# SAMW25_Xplained_Pro_EDBG.net
KiCad netlist of a schematic drawn in Altium Designer
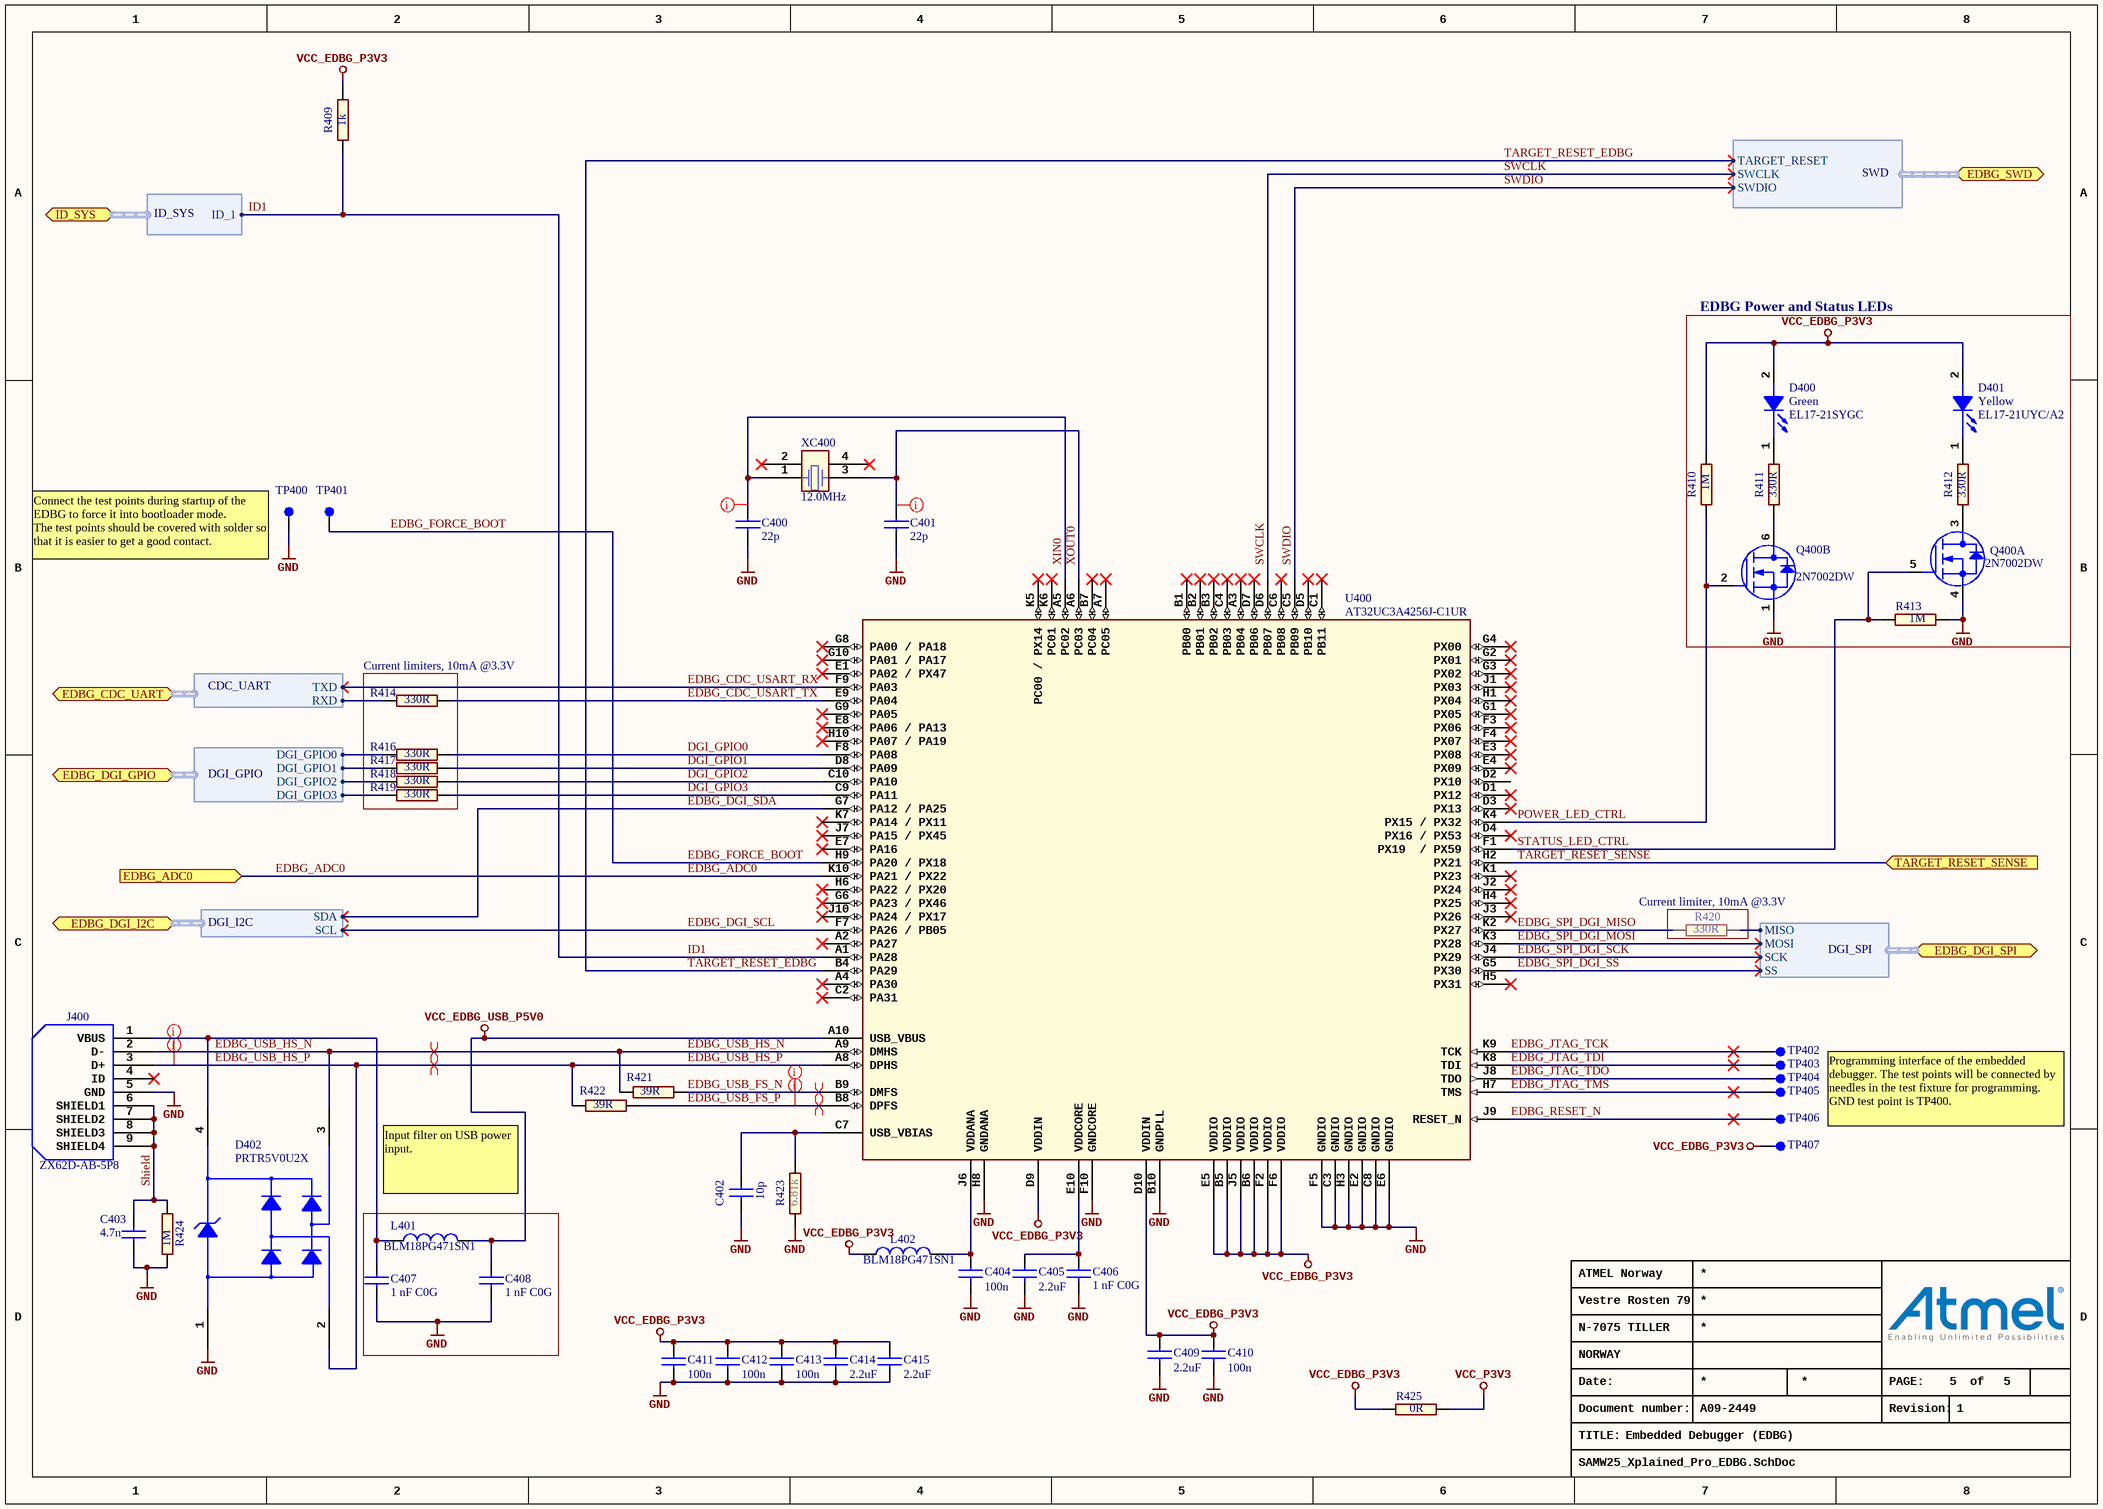
[diagram p0: SAMW25_Xplained_Pro_EDBG.SchDoc]

(export (version "E")
  (design (tool "Eeschema 10.0.6"))
  (components
    (comp (ref "C400")
      (value "22p")
      (footprint "AP1-00053")
      (description "Ceramic capacitor, SMD 0402, NP0, 50V, +/-5%")
      (fields (field (name "TOLERANCE") "50V, +/-5%") (field (name "VERIFIED BY") "Lars Helge Mo"))
      (libsource (lib "AltiumDbLib") (part "CAP-NONPOL"))
    )
    (comp (ref "C401")
      (value "22p")
      (footprint "AP1-00053")
      (description "Ceramic capacitor, SMD 0402, NP0, 50V, +/-5%")
      (fields (field (name "TOLERANCE") "50V, +/-5%") (field (name "VERIFIED BY") "Lars Helge Mo"))
      (libsource (lib "AltiumDbLib") (part "CAP-NONPOL"))
    )
    (comp (ref "C402")
      (value "10p")
      (footprint "AP1-00053")
      (description "Ceramic capacitor, SMD 0402, NP0, 50V, +/-5%")
      (fields (field (name "TOLERANCE") "50V, +/-5%") (field (name "VERIFIED BY") "Lars Helge Mo"))
      (libsource (lib "AltiumDbLib") (part "CAP-NONPOL"))
    )
    (comp (ref "C403")
      (value "4.7n")
      (footprint "AP1-00053")
      (description "Ceramic capacitor, SMD 0402, X7R, 25V, +/-10%")
      (fields
        (field (name "TOLERANCE") "25V, +/-10%")
        (field (name "Comment") "CAP-NONPOL")
        (field (name "VERIFIED BY") "Lars Helge Mo")
      )
      (libsource (lib "AltiumDbLib") (part "CAP-NONPOL"))
    )
    (comp (ref "C404")
      (value "100n")
      (footprint "AP1-00053")
      (description "Ceramic capacitor, SMD 0402, X7R, 16V, +/-10%")
      (fields
        (field (name "TOLERANCE") "16V, +/-10%")
        (field (name "MANUFACTURER") "Kemet")
        (field (name "VERIFIED BY") "Lars Helge Mo")
      )
      (libsource (lib "AltiumDbLib") (part "CAP-NONPOL"))
    )
    (comp (ref "C405")
      (value "2.2uF")
      (footprint "AP1-00053")
      (description "Ceramic capacitor, SMD 0402, X5R, 6.3V, +/-20%")
      (fields
        (field (name "TOLERANCE") "±20%")
        (field (name "MANUFACTURER") "Kemet")
        (field (name "VERIFIED BY") "Lars Helge Mo")
      )
      (libsource (lib "AltiumDbLib") (part "CAP-NONPOL"))
    )
    (comp (ref "C406")
      (value "1 nF C0G")
      (footprint "AP1-00053")
      (description "Ceramic capacitor, SMD 0402, C0G, 50V, +/-5%")
      (fields
        (field (name "TOLERANCE") "5%")
        (field (name "MANUFACTURER") "Murata")
        (field (name "VERIFIED BY") "Lars Helge Mo")
      )
      (libsource (lib "AltiumDbLib") (part "CAP-NONPOL"))
    )
    (comp (ref "C407")
      (value "1 nF C0G")
      (footprint "AP1-00053")
      (description "Ceramic capacitor, SMD 0402, C0G, 50V, +/-5%")
      (fields
        (field (name "TOLERANCE") "5%")
        (field (name "MANUFACTURER") "Murata")
        (field (name "VERIFIED BY") "Lars Helge Mo")
      )
      (libsource (lib "AltiumDbLib") (part "CAP-NONPOL"))
    )
    (comp (ref "C408")
      (value "1 nF C0G")
      (footprint "AP1-00053")
      (description "Ceramic capacitor, SMD 0402, C0G, 50V, +/-5%")
      (fields
        (field (name "TOLERANCE") "5%")
        (field (name "MANUFACTURER") "Murata")
        (field (name "VERIFIED BY") "Lars Helge Mo")
      )
      (libsource (lib "AltiumDbLib") (part "CAP-NONPOL"))
    )
    (comp (ref "C409")
      (value "2.2uF")
      (footprint "AP1-00053")
      (description "Ceramic capacitor, SMD 0402, X5R, 6.3V, +/-20%")
      (fields
        (field (name "TOLERANCE") "±20%")
        (field (name "MANUFACTURER") "Kemet")
        (field (name "VERIFIED BY") "Lars Helge Mo")
      )
      (libsource (lib "AltiumDbLib") (part "CAP-NONPOL"))
    )
    (comp (ref "C410")
      (value "100n")
      (footprint "AP1-00053")
      (description "Ceramic capacitor, SMD 0402, X7R, 16V, +/-10%")
      (fields
        (field (name "TOLERANCE") "16V, +/-10%")
        (field (name "MANUFACTURER") "Kemet")
        (field (name "VERIFIED BY") "Lars Helge Mo")
      )
      (libsource (lib "AltiumDbLib") (part "CAP-NONPOL"))
    )
    (comp (ref "C411")
      (value "100n")
      (footprint "AP1-00053")
      (description "Ceramic capacitor, SMD 0402, X7R, 16V, +/-10%")
      (fields
        (field (name "TOLERANCE") "16V, +/-10%")
        (field (name "MANUFACTURER") "Kemet")
        (field (name "VERIFIED BY") "Lars Helge Mo")
      )
      (libsource (lib "AltiumDbLib") (part "CAP-NONPOL"))
    )
    (comp (ref "C412")
      (value "100n")
      (footprint "AP1-00053")
      (description "Ceramic capacitor, SMD 0402, X7R, 16V, +/-10%")
      (fields
        (field (name "TOLERANCE") "16V, +/-10%")
        (field (name "MANUFACTURER") "Kemet")
        (field (name "VERIFIED BY") "Lars Helge Mo")
      )
      (libsource (lib "AltiumDbLib") (part "CAP-NONPOL"))
    )
    (comp (ref "C413")
      (value "100n")
      (footprint "AP1-00053")
      (description "Ceramic capacitor, SMD 0402, X7R, 16V, +/-10%")
      (fields
        (field (name "TOLERANCE") "16V, +/-10%")
        (field (name "MANUFACTURER") "Kemet")
        (field (name "VERIFIED BY") "Lars Helge Mo")
      )
      (libsource (lib "AltiumDbLib") (part "CAP-NONPOL"))
    )
    (comp (ref "C414")
      (value "2.2uF")
      (footprint "AP1-00053")
      (description "Ceramic capacitor, SMD 0402, X5R, 6.3V, +/-20%")
      (fields
        (field (name "TOLERANCE") "±20%")
        (field (name "MANUFACTURER") "Kemet")
        (field (name "VERIFIED BY") "Lars Helge Mo")
      )
      (libsource (lib "AltiumDbLib") (part "CAP-NONPOL"))
    )
    (comp (ref "C415")
      (value "2.2uF")
      (footprint "AP1-00053")
      (description "Ceramic capacitor, SMD 0402, X5R, 6.3V, +/-20%")
      (fields
        (field (name "TOLERANCE") "±20%")
        (field (name "MANUFACTURER") "Kemet")
        (field (name "VERIFIED BY") "Lars Helge Mo")
      )
      (libsource (lib "AltiumDbLib") (part "CAP-NONPOL"))
    )
    (comp (ref "D400")
      (value "Green")
      (footprint "AP4-00013")
      (description "LED, Green, Wave length=575nm, SMD 0805, ±70°")
      (fields
        (field (name "ALTIUM_VALUE") "EL17-21SYGC")
        (field (name "MANUFACTURER") "Everlight")
        (field (name "MPN") "EL17-21SYGC")
        (field (name "VERIFIED BY") "Sveinung Helgeland")
      )
      (libsource (lib "AltiumDbLib") (part "LED_12"))
    )
    (comp (ref "D401")
      (value "Yellow")
      (footprint "AP4-00013")
      (description "LED, Yellow, Wave length=591nm, SMD 0805, ±70°")
      (fields
        (field (name "ALTIUM_VALUE") "EL17-21UYC/A2")
        (field (name "MANUFACTURER") "Everlight")
        (field (name "MPN") "17-21UYC/S530-A3/TR8")
        (field (name "VERIFIED BY") "Sveinung Helgeland")
      )
      (libsource (lib "AltiumDbLib") (part "LED_12"))
    )
    (comp (ref "D402")
      (value "PRTR5V0U2X")
      (footprint "AP4-00001")
      (description "Double rail-to-rail USB ESD protection diode")
      (fields (field (name "MANUFACTURER") "Philips") (field (name "VERIFIED BY") "Lars Nordin"))
      (libsource (lib "AltiumDbLib") (part "PRTR5V0U2X"))
    )
    (comp (ref "J400")
      (value "ZX62D-AB-5P8")
      (footprint "AP8-00852")
      (description "Micro USB AB Connector, Standard SMT + DIP")
      (fields (field (name "Comment") "2,000 pieces per reel") (field (name "VERIFIED BY") "Eirik Rasmussen"))
      (libsource (lib "AltiumDbLib") (part "USB_AB"))
    )
    (comp (ref "L401")
      (value "BLM18PG471SN1")
      (footprint "AP3-00005")
      (description "SMD RF inductor 0603. Z=470Ohm (@100MHz), Max R(dc)=0.65Ohm, Max current=1A")
      (fields
        (field (name "TOLERANCE") "±25%")
        (field (name "MANUFACTURER") "Murata")
        (field (name "VERIFIED BY") "Lars Helge Mo")
      )
      (libsource (lib "AltiumDbLib") (part "INDUCTOR"))
    )
    (comp (ref "L402")
      (value "BLM18PG471SN1")
      (footprint "AP3-00005")
      (description "SMD RF inductor 0603. Z=470Ohm (@100MHz), Max R(dc)=0.65Ohm, Max current=1A")
      (fields
        (field (name "TOLERANCE") "±25%")
        (field (name "MANUFACTURER") "Murata")
        (field (name "VERIFIED BY") "Lars Helge Mo")
      )
      (libsource (lib "AltiumDbLib") (part "INDUCTOR"))
    )
    (comp (ref "Q400")
      (value "2N7002DW")
      (footprint "AP5-00001")
      (description "Dual N-Channel MOSFET, 60V, 115mA cont,RDS(ON) < 7.5 Ohm @50mA@5V, SOT-363")
      (fields
        (field (name "MANUFACTURER") "Fairchild")
        (field (name "Comment") "Same as 2N7002 but with two MOSFETs in one package")
      )
      (libsource (lib "AltiumDbLib") (part "MOSFET_DUAL_N_S2G2D1S1G1D2"))
    )
    (comp (ref "R409")
      (value "1k")
      (footprint "AP2-00000")
      (description "Thick film resistor, SMD 0402, 1/16W, 1%")
      (fields
        (field (name "TOLERANCE") "1 %")
        (field (name "Comment") "R2")
        (field (name "VERIFIED BY") "Lars Helge Mo")
      )
      (libsource (lib "") (part "R2_3"))
    )
    (comp (ref "R410")
      (value "1M")
      (footprint "AP2-00000")
      (description "Thick film resistor, SMD 0402, 1/16W, 1%")
      (fields
        (field (name "TOLERANCE") "1 %")
        (field (name "MANUFACTURER") "KOA")
        (field (name "VERIFIED BY") "Lars Helge Mo")
      )
      (libsource (lib "") (part "R2_3"))
    )
    (comp (ref "R411")
      (value "330R")
      (footprint "AP2-00000")
      (description "Thick film resistor, SMD 0402, 1/16W, 1%")
      (fields
        (field (name "TOLERANCE") "1 %")
        (field (name "Comment") "R2")
        (field (name "VERIFIED BY") "Lars Helge Mo")
      )
      (libsource (lib "") (part "R2_3"))
    )
    (comp (ref "R412")
      (value "330R")
      (footprint "AP2-00000")
      (description "Thick film resistor, SMD 0402, 1/16W, 1%")
      (fields
        (field (name "TOLERANCE") "1 %")
        (field (name "Comment") "R2")
        (field (name "VERIFIED BY") "Lars Helge Mo")
      )
      (libsource (lib "") (part "R2_3"))
    )
    (comp (ref "R413")
      (value "1M")
      (footprint "AP2-00000")
      (description "Thick film resistor, SMD 0402, 1/16W, 1%")
      (fields
        (field (name "TOLERANCE") "1 %")
        (field (name "MANUFACTURER") "KOA")
        (field (name "VERIFIED BY") "Lars Helge Mo")
      )
      (libsource (lib "") (part "R2_2"))
    )
    (comp (ref "R414")
      (value "330R")
      (footprint "AP2-00000")
      (description "Thick film resistor, SMD 0402, 1/16W, 1%")
      (fields
        (field (name "TOLERANCE") "1 %")
        (field (name "Comment") "R2")
        (field (name "VERIFIED BY") "Lars Helge Mo")
      )
      (libsource (lib "AltiumDbLib") (part "R2"))
    )
    (comp (ref "R416")
      (value "330R")
      (footprint "AP2-00000")
      (description "Thick film resistor, SMD 0402, 1/16W, 1%")
      (fields
        (field (name "TOLERANCE") "1 %")
        (field (name "Comment") "R2")
        (field (name "VERIFIED BY") "Lars Helge Mo")
      )
      (libsource (lib "AltiumDbLib") (part "R2"))
    )
    (comp (ref "R417")
      (value "330R")
      (footprint "AP2-00000")
      (description "Thick film resistor, SMD 0402, 1/16W, 1%")
      (fields
        (field (name "TOLERANCE") "1 %")
        (field (name "Comment") "R2")
        (field (name "VERIFIED BY") "Lars Helge Mo")
      )
      (libsource (lib "AltiumDbLib") (part "R2"))
    )
    (comp (ref "R418")
      (value "330R")
      (footprint "AP2-00000")
      (description "Thick film resistor, SMD 0402, 1/16W, 1%")
      (fields
        (field (name "TOLERANCE") "1 %")
        (field (name "Comment") "R2")
        (field (name "VERIFIED BY") "Lars Helge Mo")
      )
      (libsource (lib "AltiumDbLib") (part "R2"))
    )
    (comp (ref "R419")
      (value "330R")
      (footprint "AP2-00000")
      (description "Thick film resistor, SMD 0402, 1/16W, 1%")
      (fields
        (field (name "TOLERANCE") "1 %")
        (field (name "Comment") "R2")
        (field (name "VERIFIED BY") "Lars Helge Mo")
      )
      (libsource (lib "AltiumDbLib") (part "R2"))
    )
    (comp (ref "R420")
      (value "330R")
      (footprint "AP2-00000")
      (description "Thick film resistor, SMD 0402, 1/16W, 1%")
      (fields
        (field (name "TOLERANCE") "1 %")
        (field (name "Comment") "R2")
        (field (name "VERIFIED BY") "Lars Helge Mo")
      )
      (libsource (lib "AltiumDbLib") (part "R2"))
    )
    (comp (ref "R421")
      (value "39R")
      (footprint "AP2-00011")
      (description "Thick film resistor, SMD 0402, 1/16W, 1%")
      (fields
        (field (name "TOLERANCE") "1 %")
        (field (name "Comment") "R2")
        (field (name "VERIFIED BY") "Lars Helge Mo")
      )
      (libsource (lib "") (part "R2_4"))
    )
    (comp (ref "R422")
      (value "39R")
      (footprint "AP2-00011")
      (description "Thick film resistor, SMD 0402, 1/16W, 1%")
      (fields
        (field (name "TOLERANCE") "1 %")
        (field (name "Comment") "R2")
        (field (name "VERIFIED BY") "Lars Helge Mo")
      )
      (libsource (lib "") (part "R2_4"))
    )
    (comp (ref "R423")
      (value "6.81k")
      (footprint "AP2-00011")
      (description "Thick film resistor, SMD 0402, 1/16W, 1%")
      (fields
        (field (name "TOLERANCE") "1%")
        (field (name "Comment") "R2")
        (field (name "VERIFIED BY") "Lars Helge Mo")
      )
      (libsource (lib "") (part "R2_3"))
    )
    (comp (ref "R424")
      (value "1M")
      (footprint "AP2-00011")
      (description "Thick film resistor, SMD 0402, 1/16W, 1%")
      (fields
        (field (name "TOLERANCE") "1 %")
        (field (name "MANUFACTURER") "KOA")
        (field (name "VERIFIED BY") "Lars Helge Mo")
      )
      (libsource (lib "") (part "R2_1"))
    )
    (comp (ref "R425")
      (value "0R")
      (footprint "AP2-00011")
      (description "Thick film resistor, SMD 0402, 1/16W, 1%")
      (fields
        (field (name "TOLERANCE") "1 %")
        (field (name "Comment") "R2")
        (field (name "VERIFIED BY") "Lars Helge Mo")
      )
      (libsource (lib "AltiumDbLib") (part "R2"))
    )
    (comp (ref "TP400")
      (value "TESTPOINT")
      (footprint "AP8-00010")
      (description "Single SMD testpad")
      (fields (field (name "VERIFIED BY") "Sveinung Helgeland"))
      (libsource (lib "AltiumDbLib") (part "TESTPOINT"))
    )
    (comp (ref "TP401")
      (value "TESTPOINT")
      (footprint "AP8-00010")
      (description "Single SMD testpad")
      (fields (field (name "VERIFIED BY") "Sveinung Helgeland"))
      (libsource (lib "AltiumDbLib") (part "TESTPOINT"))
    )
    (comp (ref "TP402")
      (value "TESTPOINT")
      (footprint "AP8-00010")
      (description "Single SMD testpad")
      (fields (field (name "VERIFIED BY") "Sveinung Helgeland"))
      (libsource (lib "AltiumDbLib") (part "TESTPOINT"))
    )
    (comp (ref "TP403")
      (value "TESTPOINT")
      (footprint "AP8-00010")
      (description "Single SMD testpad")
      (fields (field (name "VERIFIED BY") "Sveinung Helgeland"))
      (libsource (lib "AltiumDbLib") (part "TESTPOINT"))
    )
    (comp (ref "TP404")
      (value "TESTPOINT")
      (footprint "AP8-00010")
      (description "Single SMD testpad")
      (fields (field (name "VERIFIED BY") "Sveinung Helgeland"))
      (libsource (lib "AltiumDbLib") (part "TESTPOINT"))
    )
    (comp (ref "TP405")
      (value "TESTPOINT")
      (footprint "AP8-00010")
      (description "Single SMD testpad")
      (fields (field (name "VERIFIED BY") "Sveinung Helgeland"))
      (libsource (lib "AltiumDbLib") (part "TESTPOINT"))
    )
    (comp (ref "TP406")
      (value "TESTPOINT")
      (footprint "AP8-00010")
      (description "Single SMD testpad")
      (fields (field (name "VERIFIED BY") "Sveinung Helgeland"))
      (libsource (lib "AltiumDbLib") (part "TESTPOINT"))
    )
    (comp (ref "TP407")
      (value "TESTPOINT")
      (footprint "AP8-00010")
      (description "Single SMD testpad")
      (fields (field (name "VERIFIED BY") "Sveinung Helgeland"))
      (libsource (lib "AltiumDbLib") (part "TESTPOINT"))
    )
    (comp (ref "U400")
      (value "AT32UC3A4256J-C1UR")
      (footprint "AP6-00206")
      (description "AVR 32-bit RISC MCU")
      (fields (field (name "MANUFACTURER") "ATMEL") (field (name "Comment") "100 ball VFBGA"))
      (libsource (lib "AltiumDbLib") (part "AT32UC3A4_VFBGA"))
    )
    (comp (ref "XC400")
      (value "12.0MHz")
      (footprint "AP7-00039")
      (description "Fox FQ5032B 12.0MHz SMD crystal 738B-12")
      (fields
        (field (name "TOLERANCE") "30PPM")
        (field (name "MANUFACTURER") "Fox  Electronics")
        (field (name "VERIFIED BY") "Ketil Skjerve")
      )
      (libsource (lib "AltiumDbLib") (part "CRYSTAL1324"))
    )
  )
  (nets
    (net (code "7") (name "/DGI_GPIO0") (class "Default")
      (node (ref "R416") (pin "2") (pinfunction "2_2") (pintype "passive"))
      (node (ref "U400") (pin "F8") (pinfunction "PA08_F8") (pintype "bidirectional"))
    )
    (net (code "8") (name "/DGI_GPIO1") (class "Default")
      (node (ref "R417") (pin "2") (pinfunction "2_2") (pintype "passive"))
      (node (ref "U400") (pin "D8") (pinfunction "PA09_D8") (pintype "bidirectional"))
    )
    (net (code "9") (name "/DGI_GPIO2") (class "Default")
      (node (ref "R418") (pin "2") (pinfunction "2_2") (pintype "passive"))
      (node (ref "U400") (pin "C10") (pinfunction "PA10_C10") (pintype "bidirectional"))
    )
    (net (code "10") (name "/DGI_GPIO3") (class "Default")
      (node (ref "R419") (pin "2") (pinfunction "2_2") (pintype "passive"))
      (node (ref "U400") (pin "C9") (pinfunction "PA11_C9") (pintype "bidirectional"))
    )
    (net (code "11") (name "/EDBG_ADC0") (class "Default")
      (node (ref "U400") (pin "K10") (pinfunction "PA21_/_PX22_K10") (pintype "bidirectional"))
    )
    (net (code "12") (name "/EDBG_CDC_USART_RX") (class "Default")
      (node (ref "U400") (pin "F9") (pinfunction "PA03_F9") (pintype "bidirectional+no_connect"))
    )
    (net (code "13") (name "/EDBG_CDC_USART_TX") (class "Default")
      (node (ref "R414") (pin "2") (pinfunction "2_2") (pintype "passive"))
      (node (ref "U400") (pin "E9") (pinfunction "PA04_E9") (pintype "bidirectional"))
    )
    (net (code "14") (name "/EDBG_DGI_SCL") (class "Default")
      (node (ref "U400") (pin "F7") (pinfunction "PA26_/_PB05_F7") (pintype "bidirectional+no_connect"))
    )
    (net (code "15") (name "/EDBG_DGI_SDA") (class "Default")
      (node (ref "U400") (pin "G7") (pinfunction "PA12_/_PA25_G7") (pintype "bidirectional+no_connect"))
    )
    (net (code "16") (name "/EDBG_FORCE_BOOT") (class "Default")
      (node (ref "TP401") (pin "1") (pinfunction "1_1") (pintype "passive"))
      (node (ref "U400") (pin "H9") (pinfunction "PA20_/_PX18_H9") (pintype "bidirectional"))
    )
    (net (code "17") (name "/EDBG_JTAG_TCK") (class "Default")
      (node (ref "TP402") (pin "1") (pinfunction "1_1") (pintype "passive"))
      (node (ref "U400") (pin "K9") (pinfunction "TCK_K9") (pintype "input"))
    )
    (net (code "18") (name "/EDBG_JTAG_TDI") (class "Default")
      (node (ref "TP403") (pin "1") (pinfunction "1_1") (pintype "passive"))
      (node (ref "U400") (pin "K8") (pinfunction "TDI_K8") (pintype "input"))
    )
    (net (code "19") (name "/EDBG_JTAG_TDO") (class "Default")
      (node (ref "TP404") (pin "1") (pinfunction "1_1") (pintype "passive"))
      (node (ref "U400") (pin "J8") (pinfunction "TDO_J8") (pintype "output"))
    )
    (net (code "20") (name "/EDBG_JTAG_TMS") (class "Default")
      (node (ref "TP405") (pin "1") (pinfunction "1_1") (pintype "passive"))
      (node (ref "U400") (pin "H7") (pinfunction "TMS_H7") (pintype "input"))
    )
    (net (code "21") (name "/EDBG_RESET_N") (class "Default")
      (node (ref "TP406") (pin "1") (pinfunction "1_1") (pintype "passive"))
      (node (ref "U400") (pin "J9") (pinfunction "RESET_N_J9") (pintype "input"))
    )
    (net (code "22") (name "/EDBG_SPI_DGI_MISO") (class "Default")
      (node (ref "R420") (pin "1") (pinfunction "1_1") (pintype "passive"))
      (node (ref "U400") (pin "K2") (pinfunction "PX27_K2") (pintype "bidirectional"))
    )
    (net (code "23") (name "/EDBG_SPI_DGI_MOSI") (class "Default")
      (node (ref "U400") (pin "K3") (pinfunction "PX28_K3") (pintype "bidirectional+no_connect"))
    )
    (net (code "24") (name "/EDBG_SPI_DGI_SCK") (class "Default")
      (node (ref "U400") (pin "J4") (pinfunction "PX29_J4") (pintype "bidirectional+no_connect"))
    )
    (net (code "25") (name "/EDBG_SPI_DGI_SS") (class "Default")
      (node (ref "U400") (pin "G5") (pinfunction "PX30_G5") (pintype "bidirectional+no_connect"))
    )
    (net (code "26") (name "/EDBG_USB_FS_N") (class "Default")
      (node (ref "R421") (pin "2") (pinfunction "2_2") (pintype "passive"))
      (node (ref "U400") (pin "B9") (pinfunction "DMFS_B9") (pintype "bidirectional"))
    )
    (net (code "27") (name "/EDBG_USB_FS_P") (class "Default")
      (node (ref "R422") (pin "2") (pinfunction "2_2") (pintype "passive"))
      (node (ref "U400") (pin "B8") (pinfunction "DPFS_B8") (pintype "bidirectional"))
    )
    (net (code "28") (name "/EDBG_USB_HS_N") (class "Default")
      (node (ref "D402") (pin "3") (pinfunction "I/O_2_3") (pintype "passive"))
      (node (ref "J400") (pin "2") (pinfunction "D-_2") (pintype "passive"))
      (node (ref "R421") (pin "1") (pinfunction "1_1") (pintype "passive"))
      (node (ref "U400") (pin "A9") (pinfunction "DMHS_A9") (pintype "bidirectional"))
    )
    (net (code "29") (name "/EDBG_USB_HS_P") (class "Default")
      (node (ref "D402") (pin "2") (pinfunction "I/O_1_2") (pintype "passive"))
      (node (ref "J400") (pin "3") (pinfunction "D+_3") (pintype "passive"))
      (node (ref "R422") (pin "1") (pinfunction "1_1") (pintype "passive"))
      (node (ref "U400") (pin "A8") (pinfunction "DPHS_A8") (pintype "bidirectional"))
    )
    (net (code "30") (name "/ID1") (class "Default")
      (node (ref "R409") (pin "1") (pinfunction "1_1") (pintype "passive"))
      (node (ref "U400") (pin "A1") (pinfunction "PA28_A1") (pintype "bidirectional"))
    )
    (net (code "31") (name "/MISO") (class "Default")
      (node (ref "R420") (pin "2") (pinfunction "2_2") (pintype "passive"))
    )
    (net (code "32") (name "/POWER_LED_CTRL") (class "Default")
      (node (ref "Q400") (pin "2") (pinfunction "G2_2") (pintype "passive"))
      (node (ref "R410") (pin "1") (pinfunction "1_1") (pintype "passive"))
      (node (ref "U400") (pin "K4") (pinfunction "PX15_/_PX32_K4") (pintype "bidirectional"))
    )
    (net (code "33") (name "/RXD") (class "Default")
      (node (ref "R414") (pin "1") (pinfunction "1_1") (pintype "passive"))
    )
    (net (code "34") (name "/STATUS_LED_CTRL") (class "Default")
      (node (ref "Q400") (pin "5") (pinfunction "G1_5") (pintype "passive"))
      (node (ref "R413") (pin "2") (pinfunction "2_2") (pintype "passive"))
      (node (ref "U400") (pin "F1") (pinfunction "PX19__/_PX59_F1") (pintype "bidirectional"))
    )
    (net (code "35") (name "/SWCLK") (class "Default")
      (node (ref "U400") (pin "D6") (pinfunction "PB07_D6") (pintype "bidirectional+no_connect"))
    )
    (net (code "36") (name "/SWDIO") (class "Default")
      (node (ref "U400") (pin "C5") (pinfunction "PB09_C5") (pintype "bidirectional+no_connect"))
    )
    (net (code "37") (name "/Shield") (class "Default")
      (node (ref "C403") (pin "2") (pinfunction "2_2") (pintype "passive"))
      (node (ref "J400") (pin "6") (pinfunction "SHIELD1_6") (pintype "passive"))
      (node (ref "J400") (pin "7") (pinfunction "SHIELD2_7") (pintype "passive"))
      (node (ref "J400") (pin "8") (pinfunction "SHIELD3_8") (pintype "passive"))
      (node (ref "J400") (pin "9") (pinfunction "SHIELD4_9") (pintype "passive"))
      (node (ref "R424") (pin "2") (pinfunction "2_2") (pintype "passive"))
    )
    (net (code "38") (name "/TARGET_RESET_EDBG") (class "Default")
      (node (ref "U400") (pin "B4") (pinfunction "PA29_B4") (pintype "bidirectional+no_connect"))
    )
    (net (code "39") (name "/TARGET_RESET_SENSE") (class "Default")
      (node (ref "U400") (pin "H2") (pinfunction "PX21_H2") (pintype "bidirectional"))
    )
    (net (code "40") (name "/XIN0") (class "Default")
      (node (ref "C400") (pin "1") (pinfunction "1_1") (pintype "passive"))
      (node (ref "U400") (pin "A5") (pinfunction "PC02_A5") (pintype "bidirectional"))
      (node (ref "XC400") (pin "1") (pinfunction "1_1") (pintype "passive"))
    )
    (net (code "41") (name "/XOUT0") (class "Default")
      (node (ref "C401") (pin "1") (pinfunction "1_1") (pintype "passive"))
      (node (ref "U400") (pin "A6") (pinfunction "PC03_A6") (pintype "bidirectional"))
      (node (ref "XC400") (pin "3") (pinfunction "3_3") (pintype "passive"))
    )
    (net (code "48") (name "GND") (class "Default")
      (node (ref "C400") (pin "2") (pinfunction "2_2") (pintype "passive"))
      (node (ref "C401") (pin "2") (pinfunction "2_2") (pintype "passive"))
      (node (ref "C402") (pin "2") (pinfunction "2_2") (pintype "passive"))
      (node (ref "C403") (pin "1") (pinfunction "1_1") (pintype "passive"))
      (node (ref "C404") (pin "2") (pinfunction "2_2") (pintype "passive"))
      (node (ref "C405") (pin "2") (pinfunction "2_2") (pintype "passive"))
      (node (ref "C406") (pin "2") (pinfunction "2_2") (pintype "passive"))
      (node (ref "C407") (pin "2") (pinfunction "2_2") (pintype "passive"))
      (node (ref "C408") (pin "2") (pinfunction "2_2") (pintype "passive"))
      (node (ref "C409") (pin "2") (pinfunction "2_2") (pintype "passive"))
      (node (ref "C410") (pin "2") (pinfunction "2_2") (pintype "passive"))
      (node (ref "C411") (pin "2") (pinfunction "2_2") (pintype "passive"))
      (node (ref "C412") (pin "2") (pinfunction "2_2") (pintype "passive"))
      (node (ref "C413") (pin "2") (pinfunction "2_2") (pintype "passive"))
      (node (ref "C414") (pin "2") (pinfunction "2_2") (pintype "passive"))
      (node (ref "C415") (pin "2") (pinfunction "2_2") (pintype "passive"))
      (node (ref "D402") (pin "1") (pinfunction "GND_1") (pintype "passive"))
      (node (ref "J400") (pin "5") (pinfunction "GND_5") (pintype "passive"))
      (node (ref "Q400") (pin "1") (pinfunction "S2_1") (pintype "passive"))
      (node (ref "Q400") (pin "4") (pinfunction "S1_4") (pintype "passive"))
      (node (ref "R413") (pin "1") (pinfunction "1_1") (pintype "passive"))
      (node (ref "R423") (pin "1") (pinfunction "1_1") (pintype "passive"))
      (node (ref "R424") (pin "1") (pinfunction "1_1") (pintype "passive"))
      (node (ref "TP400") (pin "1") (pinfunction "1_1") (pintype "passive"))
      (node (ref "U400") (pin "B10") (pinfunction "GNDPLL_B10") (pintype "power_in"))
      (node (ref "U400") (pin "C3") (pinfunction "GNDIO_C3") (pintype "power_in"))
      (node (ref "U400") (pin "C8") (pinfunction "GNDIO_C8") (pintype "power_in"))
      (node (ref "U400") (pin "E2") (pinfunction "GNDIO_E2") (pintype "power_in"))
      (node (ref "U400") (pin "E6") (pinfunction "GNDIO_E6") (pintype "power_in"))
      (node (ref "U400") (pin "F10") (pinfunction "GNDCORE_F10") (pintype "power_in"))
      (node (ref "U400") (pin "F5") (pinfunction "GNDIO_F5") (pintype "power_in"))
      (node (ref "U400") (pin "H3") (pinfunction "GNDIO_H3") (pintype "power_in"))
      (node (ref "U400") (pin "H8") (pinfunction "GNDANA_H8") (pintype "power_in"))
    )
    (net (code "49") (name "Net-(D400-CATHODE)") (class "Default")
      (node (ref "D400") (pin "1") (pinfunction "CATHODE_1") (pintype "passive"))
      (node (ref "R411") (pin "2") (pinfunction "2_2") (pintype "passive"))
    )
    (net (code "50") (name "Net-(D401-CATHODE)") (class "Default")
      (node (ref "D401") (pin "1") (pinfunction "CATHODE_1") (pintype "passive"))
      (node (ref "R412") (pin "2") (pinfunction "2_2") (pintype "passive"))
    )
    (net (code "51") (name "Net-(D402-VCC)") (class "Default")
      (node (ref "C407") (pin "1") (pinfunction "1_1") (pintype "passive"))
      (node (ref "D402") (pin "4") (pinfunction "VCC_4") (pintype "passive"))
      (node (ref "J400") (pin "1") (pinfunction "VBUS_1") (pintype "passive"))
      (node (ref "L401") (pin "1") (pinfunction "1_1") (pintype "passive"))
    )
    (net (code "52") (name "Net-(Q400A-D1)") (class "Default")
      (node (ref "Q400") (pin "3") (pinfunction "D1_3") (pintype "passive"))
      (node (ref "R412") (pin "1") (pinfunction "1_1") (pintype "passive"))
    )
    (net (code "53") (name "Net-(Q400B-D2)") (class "Default")
      (node (ref "Q400") (pin "6") (pinfunction "D2_6") (pintype "passive"))
      (node (ref "R411") (pin "1") (pinfunction "1_1") (pintype "passive"))
    )
    (net (code "54") (name "Net-(U400-USB_VBIAS)") (class "Default")
      (node (ref "C402") (pin "1") (pinfunction "1_1") (pintype "passive"))
      (node (ref "R423") (pin "2") (pinfunction "2_2") (pintype "passive"))
      (node (ref "U400") (pin "C7") (pinfunction "USB_VBIAS_C7") (pintype "power_in"))
    )
    (net (code "55") (name "Net-(U400-VDDANA)") (class "Default")
      (node (ref "C404") (pin "1") (pinfunction "1_1") (pintype "passive"))
      (node (ref "L402") (pin "2") (pinfunction "2_2") (pintype "passive"))
      (node (ref "U400") (pin "J6") (pinfunction "VDDANA_J6") (pintype "power_in"))
    )
    (net (code "56") (name "Net-(U400-VDDCORE)") (class "Default")
      (node (ref "C405") (pin "1") (pinfunction "1_1") (pintype "passive"))
      (node (ref "C406") (pin "1") (pinfunction "1_1") (pintype "passive"))
      (node (ref "U400") (pin "E10") (pinfunction "VDDCORE_E10") (pintype "power_in"))
    )
    (net (code "57") (name "VCC_EDBG_P3V3") (class "Default")
      (node (ref "C409") (pin "1") (pinfunction "1_1") (pintype "passive"))
      (node (ref "C410") (pin "1") (pinfunction "1_1") (pintype "passive"))
      (node (ref "C411") (pin "1") (pinfunction "1_1") (pintype "passive"))
      (node (ref "C412") (pin "1") (pinfunction "1_1") (pintype "passive"))
      (node (ref "C413") (pin "1") (pinfunction "1_1") (pintype "passive"))
      (node (ref "C414") (pin "1") (pinfunction "1_1") (pintype "passive"))
      (node (ref "C415") (pin "1") (pinfunction "1_1") (pintype "passive"))
      (node (ref "D400") (pin "2") (pinfunction "ANODE_2") (pintype "passive"))
      (node (ref "D401") (pin "2") (pinfunction "ANODE_2") (pintype "passive"))
      (node (ref "L402") (pin "1") (pinfunction "1_1") (pintype "passive"))
      (node (ref "R409") (pin "2") (pinfunction "2_2") (pintype "passive"))
      (node (ref "R410") (pin "2") (pinfunction "2_2") (pintype "passive"))
      (node (ref "R425") (pin "1") (pinfunction "1_1") (pintype "passive"))
      (node (ref "TP407") (pin "1") (pinfunction "1_1") (pintype "passive"))
      (node (ref "U400") (pin "B5") (pinfunction "VDDIO_B5") (pintype "power_in"))
      (node (ref "U400") (pin "B6") (pinfunction "VDDIO_B6") (pintype "power_in"))
      (node (ref "U400") (pin "D10") (pinfunction "VDDIN_D10") (pintype "power_in"))
      (node (ref "U400") (pin "D9") (pinfunction "VDDIN_D9") (pintype "power_in"))
      (node (ref "U400") (pin "E5") (pinfunction "VDDIO_E5") (pintype "power_in"))
      (node (ref "U400") (pin "F2") (pinfunction "VDDIO_F2") (pintype "power_in"))
      (node (ref "U400") (pin "F6") (pinfunction "VDDIO_F6") (pintype "power_in"))
      (node (ref "U400") (pin "J5") (pinfunction "VDDIO_J5") (pintype "power_in"))
    )
    (net (code "58") (name "VCC_EDBG_USB_P5V0") (class "Default")
      (node (ref "C408") (pin "1") (pinfunction "1_1") (pintype "passive"))
      (node (ref "L401") (pin "2") (pinfunction "2_2") (pintype "passive"))
      (node (ref "U400") (pin "A10") (pinfunction "USB_VBUS_A10") (pintype "power_in"))
    )
    (net (code "59") (name "VCC_P3V3") (class "Default")
      (node (ref "R425") (pin "2") (pinfunction "2_2") (pintype "passive"))
    )
    (net (code "60") (name "unconnected-(J400-ID-Pad4)") (class "Default")
      (node (ref "J400") (pin "4") (pinfunction "ID_4") (pintype "passive+no_connect"))
    )
    (net (code "61") (name "unconnected-(R416-Pad1)") (class "Default")
      (node (ref "R416") (pin "1") (pinfunction "1_1") (pintype "passive"))
    )
    (net (code "62") (name "unconnected-(R417-Pad1)") (class "Default")
      (node (ref "R417") (pin "1") (pinfunction "1_1") (pintype "passive"))
    )
    (net (code "63") (name "unconnected-(R418-Pad1)") (class "Default")
      (node (ref "R418") (pin "1") (pinfunction "1_1") (pintype "passive"))
    )
    (net (code "64") (name "unconnected-(R419-Pad1)") (class "Default")
      (node (ref "R419") (pin "1") (pinfunction "1_1") (pintype "passive"))
    )
    (net (code "65") (name "unconnected-(U400-PA00_{slash}_PA18-PadG8)") (class "Default")
      (node (ref "U400") (pin "G8") (pinfunction "PA00_/_PA18_G8") (pintype "bidirectional+no_connect"))
    )
    (net (code "66") (name "unconnected-(U400-PA01_{slash}_PA17-PadG10)") (class "Default")
      (node (ref "U400") (pin "G10") (pinfunction "PA01_/_PA17_G10") (pintype "bidirectional+no_connect"))
    )
    (net (code "67") (name "unconnected-(U400-PA02_{slash}_PX47-PadE1)") (class "Default")
      (node (ref "U400") (pin "E1") (pinfunction "PA02_/_PX47_E1") (pintype "bidirectional+no_connect"))
    )
    (net (code "68") (name "unconnected-(U400-PA05-PadG9)") (class "Default")
      (node (ref "U400") (pin "G9") (pinfunction "PA05_G9") (pintype "bidirectional+no_connect"))
    )
    (net (code "69") (name "unconnected-(U400-PA06_{slash}_PA13-PadE8)") (class "Default")
      (node (ref "U400") (pin "E8") (pinfunction "PA06_/_PA13_E8") (pintype "bidirectional+no_connect"))
    )
    (net (code "70") (name "unconnected-(U400-PA07_{slash}_PA19-PadH10)") (class "Default")
      (node (ref "U400") (pin "H10") (pinfunction "PA07_/_PA19_H10") (pintype "bidirectional+no_connect"))
    )
    (net (code "71") (name "unconnected-(U400-PA14_{slash}_PX11-PadK7)") (class "Default")
      (node (ref "U400") (pin "K7") (pinfunction "PA14_/_PX11_K7") (pintype "bidirectional+no_connect"))
    )
    (net (code "72") (name "unconnected-(U400-PA15_{slash}_PX45-PadJ7)") (class "Default")
      (node (ref "U400") (pin "J7") (pinfunction "PA15_/_PX45_J7") (pintype "bidirectional+no_connect"))
    )
    (net (code "73") (name "unconnected-(U400-PA16-PadE7)") (class "Default")
      (node (ref "U400") (pin "E7") (pinfunction "PA16_E7") (pintype "bidirectional+no_connect"))
    )
    (net (code "74") (name "unconnected-(U400-PA22_{slash}_PX20-PadH6)") (class "Default")
      (node (ref "U400") (pin "H6") (pinfunction "PA22_/_PX20_H6") (pintype "bidirectional+no_connect"))
    )
    (net (code "75") (name "unconnected-(U400-PA23_{slash}_PX46-PadG6)") (class "Default")
      (node (ref "U400") (pin "G6") (pinfunction "PA23_/_PX46_G6") (pintype "bidirectional+no_connect"))
    )
    (net (code "76") (name "unconnected-(U400-PA24_{slash}_PX17-PadJ10)") (class "Default")
      (node (ref "U400") (pin "J10") (pinfunction "PA24_/_PX17_J10") (pintype "bidirectional+no_connect"))
    )
    (net (code "77") (name "unconnected-(U400-PA27-PadA2)") (class "Default")
      (node (ref "U400") (pin "A2") (pinfunction "PA27_A2") (pintype "bidirectional+no_connect"))
    )
    (net (code "78") (name "unconnected-(U400-PA30-PadA4)") (class "Default")
      (node (ref "U400") (pin "A4") (pinfunction "PA30_A4") (pintype "bidirectional+no_connect"))
    )
    (net (code "79") (name "unconnected-(U400-PA31-PadC2)") (class "Default")
      (node (ref "U400") (pin "C2") (pinfunction "PA31_C2") (pintype "bidirectional+no_connect"))
    )
    (net (code "80") (name "unconnected-(U400-PB00-PadB1)") (class "Default")
      (node (ref "U400") (pin "B1") (pinfunction "PB00_B1") (pintype "bidirectional+no_connect"))
    )
    (net (code "81") (name "unconnected-(U400-PB01-PadB2)") (class "Default")
      (node (ref "U400") (pin "B2") (pinfunction "PB01_B2") (pintype "bidirectional+no_connect"))
    )
    (net (code "82") (name "unconnected-(U400-PB02-PadB3)") (class "Default")
      (node (ref "U400") (pin "B3") (pinfunction "PB02_B3") (pintype "bidirectional+no_connect"))
    )
    (net (code "83") (name "unconnected-(U400-PB03-PadC4)") (class "Default")
      (node (ref "U400") (pin "C4") (pinfunction "PB03_C4") (pintype "bidirectional+no_connect"))
    )
    (net (code "84") (name "unconnected-(U400-PB04-PadA3)") (class "Default")
      (node (ref "U400") (pin "A3") (pinfunction "PB04_A3") (pintype "bidirectional+no_connect"))
    )
    (net (code "85") (name "unconnected-(U400-PB06-PadD7)") (class "Default")
      (node (ref "U400") (pin "D7") (pinfunction "PB06_D7") (pintype "bidirectional+no_connect"))
    )
    (net (code "86") (name "unconnected-(U400-PB08-PadC6)") (class "Default")
      (node (ref "U400") (pin "C6") (pinfunction "PB08_C6") (pintype "bidirectional+no_connect"))
    )
    (net (code "87") (name "unconnected-(U400-PB10-PadD5)") (class "Default")
      (node (ref "U400") (pin "D5") (pinfunction "PB10_D5") (pintype "bidirectional+no_connect"))
    )
    (net (code "88") (name "unconnected-(U400-PB11-PadC1)") (class "Default")
      (node (ref "U400") (pin "C1") (pinfunction "PB11_C1") (pintype "bidirectional+no_connect"))
    )
    (net (code "89") (name "unconnected-(U400-PC00_{slash}_PX14-PadK5)") (class "Default")
      (node (ref "U400") (pin "K5") (pinfunction "PC00_/_PX14_K5") (pintype "bidirectional+no_connect"))
    )
    (net (code "90") (name "unconnected-(U400-PC01-PadK6)") (class "Default")
      (node (ref "U400") (pin "K6") (pinfunction "PC01_K6") (pintype "bidirectional+no_connect"))
    )
    (net (code "91") (name "unconnected-(U400-PC04-PadB7)") (class "Default")
      (node (ref "U400") (pin "B7") (pinfunction "PC04_B7") (pintype "bidirectional+no_connect"))
    )
    (net (code "92") (name "unconnected-(U400-PC05-PadA7)") (class "Default")
      (node (ref "U400") (pin "A7") (pinfunction "PC05_A7") (pintype "bidirectional+no_connect"))
    )
    (net (code "93") (name "unconnected-(U400-PX00-PadG4)") (class "Default")
      (node (ref "U400") (pin "G4") (pinfunction "PX00_G4") (pintype "bidirectional+no_connect"))
    )
    (net (code "94") (name "unconnected-(U400-PX01-PadG2)") (class "Default")
      (node (ref "U400") (pin "G2") (pinfunction "PX01_G2") (pintype "bidirectional+no_connect"))
    )
    (net (code "95") (name "unconnected-(U400-PX02-PadG3)") (class "Default")
      (node (ref "U400") (pin "G3") (pinfunction "PX02_G3") (pintype "bidirectional+no_connect"))
    )
    (net (code "96") (name "unconnected-(U400-PX03-PadJ1)") (class "Default")
      (node (ref "U400") (pin "J1") (pinfunction "PX03_J1") (pintype "bidirectional+no_connect"))
    )
    (net (code "97") (name "unconnected-(U400-PX04-PadH1)") (class "Default")
      (node (ref "U400") (pin "H1") (pinfunction "PX04_H1") (pintype "bidirectional+no_connect"))
    )
    (net (code "98") (name "unconnected-(U400-PX05-PadG1)") (class "Default")
      (node (ref "U400") (pin "G1") (pinfunction "PX05_G1") (pintype "bidirectional+no_connect"))
    )
    (net (code "99") (name "unconnected-(U400-PX06-PadF3)") (class "Default")
      (node (ref "U400") (pin "F3") (pinfunction "PX06_F3") (pintype "bidirectional+no_connect"))
    )
    (net (code "100") (name "unconnected-(U400-PX07-PadF4)") (class "Default")
      (node (ref "U400") (pin "F4") (pinfunction "PX07_F4") (pintype "bidirectional+no_connect"))
    )
    (net (code "101") (name "unconnected-(U400-PX08-PadE3)") (class "Default")
      (node (ref "U400") (pin "E3") (pinfunction "PX08_E3") (pintype "bidirectional+no_connect"))
    )
    (net (code "102") (name "unconnected-(U400-PX09-PadE4)") (class "Default")
      (node (ref "U400") (pin "E4") (pinfunction "PX09_E4") (pintype "bidirectional+no_connect"))
    )
    (net (code "103") (name "unconnected-(U400-PX10-PadD2)") (class "Default")
      (node (ref "U400") (pin "D2") (pinfunction "PX10_D2") (pintype "bidirectional"))
    )
    (net (code "104") (name "unconnected-(U400-PX12-PadD1)") (class "Default")
      (node (ref "U400") (pin "D1") (pinfunction "PX12_D1") (pintype "bidirectional+no_connect"))
    )
    (net (code "105") (name "unconnected-(U400-PX13-PadD3)") (class "Default")
      (node (ref "U400") (pin "D3") (pinfunction "PX13_D3") (pintype "bidirectional+no_connect"))
    )
    (net (code "106") (name "unconnected-(U400-PX16_{slash}_PX53-PadD4)") (class "Default")
      (node (ref "U400") (pin "D4") (pinfunction "PX16_/_PX53_D4") (pintype "bidirectional+no_connect"))
    )
    (net (code "107") (name "unconnected-(U400-PX23-PadK1)") (class "Default")
      (node (ref "U400") (pin "K1") (pinfunction "PX23_K1") (pintype "bidirectional+no_connect"))
    )
    (net (code "108") (name "unconnected-(U400-PX24-PadJ2)") (class "Default")
      (node (ref "U400") (pin "J2") (pinfunction "PX24_J2") (pintype "bidirectional+no_connect"))
    )
    (net (code "109") (name "unconnected-(U400-PX25-PadH4)") (class "Default")
      (node (ref "U400") (pin "H4") (pinfunction "PX25_H4") (pintype "bidirectional+no_connect"))
    )
    (net (code "110") (name "unconnected-(U400-PX26-PadJ3)") (class "Default")
      (node (ref "U400") (pin "J3") (pinfunction "PX26_J3") (pintype "bidirectional+no_connect"))
    )
    (net (code "111") (name "unconnected-(U400-PX31-PadH5)") (class "Default")
      (node (ref "U400") (pin "H5") (pinfunction "PX31_H5") (pintype "bidirectional+no_connect"))
    )
    (net (code "112") (name "unconnected-(XC400-Pad2)") (class "Default")
      (node (ref "XC400") (pin "2") (pinfunction "2_2") (pintype "passive+no_connect"))
    )
    (net (code "113") (name "unconnected-(XC400-Pad4)") (class "Default")
      (node (ref "XC400") (pin "4") (pinfunction "4_4") (pintype "passive+no_connect"))
    )
  )
)
